# Driver_rect.net
KiCad netlist of a schematic drawn in Altium Designer
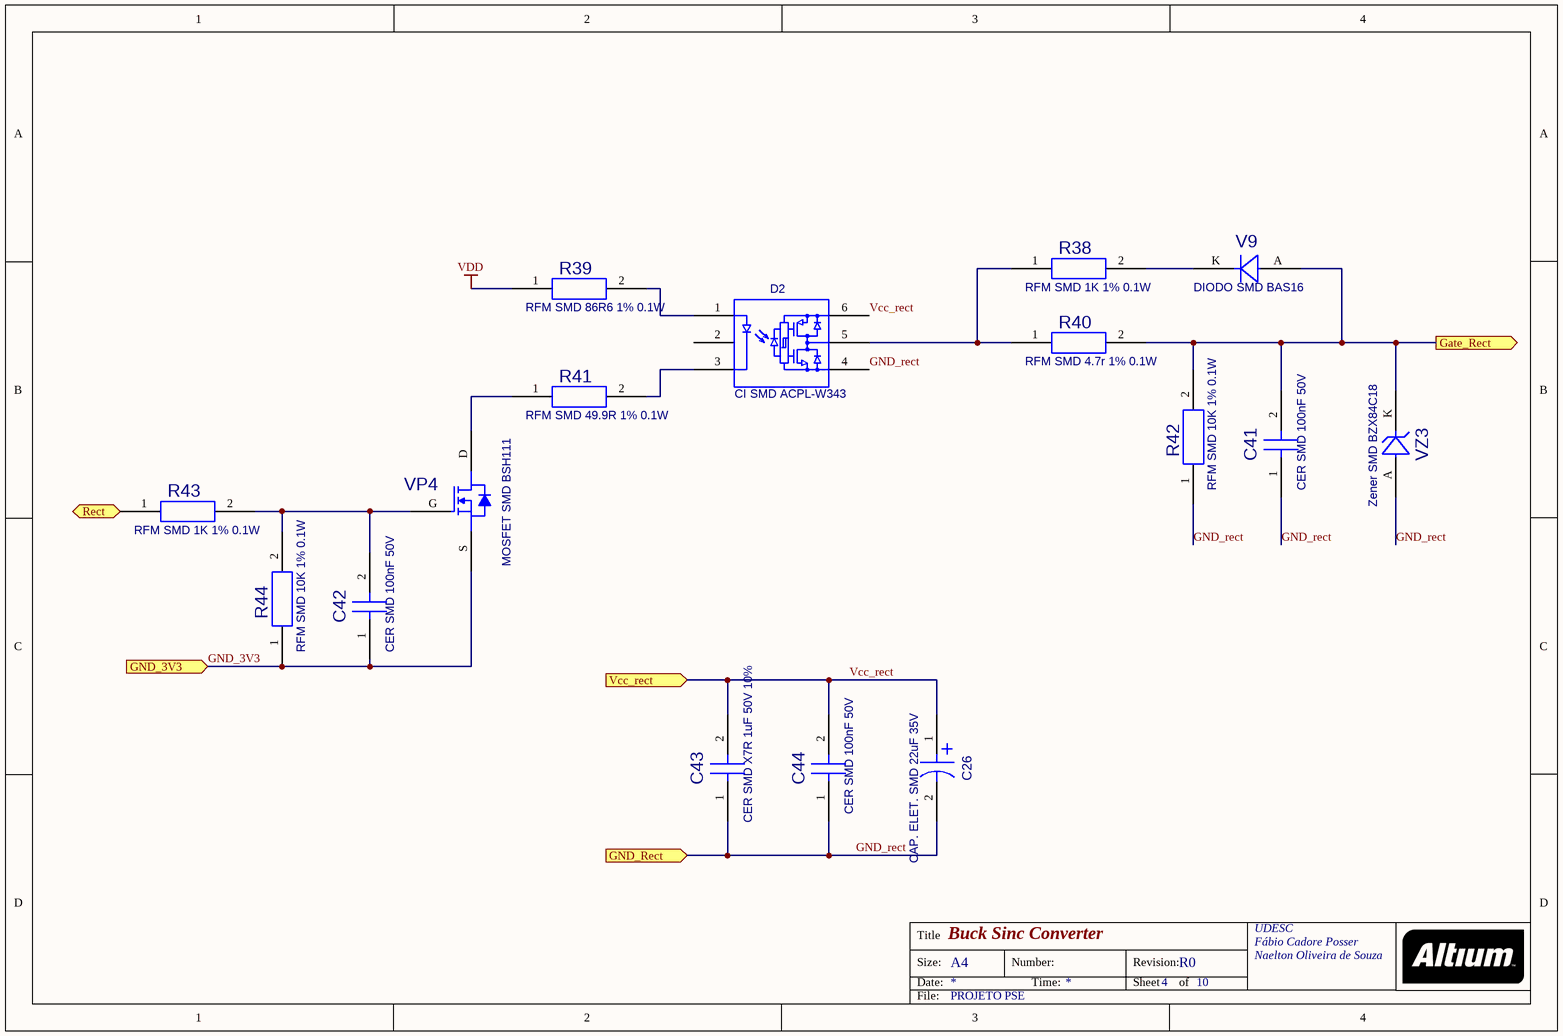
[diagram p0: Driver_rect.SchDoc]

(export (version "E")
  (design (tool "Eeschema 10.0.6"))
  (components
    (comp (ref "C26")
      (value "CAP. ELET. SMD 22uF 35V")
      (footprint "CAP UUD CR 5X5.8")
      (fields (field (name "Comment") "11690909"))
      (libsource (lib "Conv_buck_R0") (part "11690909"))
    )
    (comp (ref "C41")
      (value "CER SMD 100nF 50V")
      (footprint "C0805_R_V0")
      (fields (field (name "Comment") "10192075"))
      (libsource (lib "Buck_Converter") (part "10192075"))
    )
    (comp (ref "C42")
      (value "CER SMD 100nF 50V")
      (footprint "C0805_R_V0")
      (fields (field (name "Comment") "10192075"))
      (libsource (lib "Buck_Converter") (part "10192075"))
    )
    (comp (ref "C43")
      (value "CER SMD X7R 1uF 50V 10%")
      (footprint "C0805_R_V0")
      (fields (field (name "Comment") "11736520"))
      (libsource (lib "Buck_Converter") (part "11736520"))
    )
    (comp (ref "C44")
      (value "CER SMD 100nF 50V")
      (footprint "C0805_R_V0")
      (fields (field (name "Comment") "10192075"))
      (libsource (lib "Buck_Converter") (part "10192075"))
    )
    (comp (ref "D2")
      (value "CI SMD ACPL-W343")
      (footprint "SO-6 (11.5 MM)")
      (fields (field (name "Comment") "12544475"))
      (libsource (lib "Buck_Converter") (part "12544475"))
    )
    (comp (ref "R38")
      (value "RFM SMD 1K 1% 0.1W")
      (footprint "R0805_R_V0")
      (fields (field (name "Comment") "10118077"))
      (libsource (lib "Buck_Converter") (part "10118077"))
    )
    (comp (ref "R39")
      (value "RFM SMD 86R6 1% 0.1W")
      (footprint "R0805_R_V0")
      (fields (field (name "Comment") "10192050"))
      (libsource (lib "Buck_Converter") (part "10118077"))
    )
    (comp (ref "R40")
      (value "RFM SMD 4.7r 1% 0.1W")
      (footprint "R0805_R_V0")
      (fields (field (name "Comment") "10192015"))
      (libsource (lib "Buck_Converter") (part "10118077"))
    )
    (comp (ref "R41")
      (value "RFM SMD 49.9R 1% 0.1W")
      (footprint "R0805_R_V0")
      (fields (field (name "Comment") "10192035"))
      (libsource (lib "Buck_Converter") (part "10118077"))
    )
    (comp (ref "R42")
      (value "RFM SMD 10K 1% 0.1W")
      (footprint "R0805_R_V0")
      (fields (field (name "Comment") "10118076"))
      (libsource (lib "Buck_Converter") (part "10118077"))
    )
    (comp (ref "R43")
      (value "RFM SMD 1K 1% 0.1W")
      (footprint "R0805_R_V0")
      (fields (field (name "Comment") "10118077"))
      (libsource (lib "Buck_Converter") (part "10118077"))
    )
    (comp (ref "R44")
      (value "RFM SMD 10K 1% 0.1W")
      (footprint "R0805_R_V0")
      (fields (field (name "Comment") "10118076"))
      (libsource (lib "Buck_Converter") (part "10118077"))
    )
    (comp (ref "V9")
      (value "DIODO SMD BAS16")
      (footprint "SOT23A")
      (fields (field (name "Comment") "10261302"))
      (libsource (lib "Buck_Converter") (part "10261302"))
    )
    (comp (ref "VP4")
      (value "MOSFET SMD BSH111")
      (footprint "MOS_SOT23A")
      (fields (field (name "Comment") "11110327"))
      (libsource (lib "Buck_Converter") (part "11110327"))
    )
    (comp (ref "VZ3")
      (value "Zener SMD BZX84C18")
      (footprint "ZEN_SOT23A")
      (description "Zener  SMD BZX84C18")
      (fields (field (name "Comment") "10050447"))
      (libsource (lib "Buck_Converter") (part "10050447"))
    )
  )
  (nets
    (net (code "1") (name "/GND_3V3") (class "Default")
      (node (ref "C42") (pin "1") (pinfunction "1_1") (pintype "passive"))
      (node (ref "R44") (pin "1") (pinfunction "1_1") (pintype "passive"))
      (node (ref "VP4") (pin "S") (pinfunction "S_S") (pintype "passive"))
    )
    (net (code "2") (name "/GND_rect") (class "Default")
      (node (ref "C26") (pin "2") (pinfunction "2_2") (pintype "passive"))
      (node (ref "C41") (pin "1") (pinfunction "1_1") (pintype "passive"))
      (node (ref "C43") (pin "1") (pinfunction "1_1") (pintype "passive"))
      (node (ref "C44") (pin "1") (pinfunction "1_1") (pintype "passive"))
      (node (ref "D2") (pin "4") (pinfunction "VEE_4") (pintype "passive"))
      (node (ref "R42") (pin "1") (pinfunction "1_1") (pintype "passive"))
      (node (ref "VZ3") (pin "A") (pinfunction "A_A") (pintype "passive"))
    )
    (net (code "3") (name "/Gate_Rect") (class "Default")
      (node (ref "C41") (pin "2") (pinfunction "2_2") (pintype "passive"))
      (node (ref "R40") (pin "2") (pinfunction "2_2") (pintype "passive"))
      (node (ref "R42") (pin "2") (pinfunction "2_2") (pintype "passive"))
      (node (ref "V9") (pin "A") (pinfunction "A_A") (pintype "passive"))
      (node (ref "VZ3") (pin "K") (pinfunction "K_K") (pintype "passive"))
    )
    (net (code "4") (name "/Rect") (class "Default")
      (node (ref "R43") (pin "1") (pinfunction "1_1") (pintype "passive"))
    )
    (net (code "5") (name "/Vcc_rect") (class "Default")
      (node (ref "C26") (pin "1") (pinfunction "1_1") (pintype "passive"))
      (node (ref "C43") (pin "2") (pinfunction "2_2") (pintype "passive"))
      (node (ref "C44") (pin "2") (pinfunction "2_2") (pintype "passive"))
      (node (ref "D2") (pin "6") (pinfunction "VCC_6") (pintype "passive"))
    )
    (net (code "6") (name "Net-(C42-Pad2)") (class "Default")
      (node (ref "C42") (pin "2") (pinfunction "2_2") (pintype "passive"))
      (node (ref "R43") (pin "2") (pinfunction "2_2") (pintype "passive"))
      (node (ref "R44") (pin "2") (pinfunction "2_2") (pintype "passive"))
      (node (ref "VP4") (pin "G") (pinfunction "G_G") (pintype "passive"))
    )
    (net (code "7") (name "Net-(D2-A)") (class "Default")
      (node (ref "D2") (pin "1") (pinfunction "A_1") (pintype "passive"))
      (node (ref "R39") (pin "2") (pinfunction "2_2") (pintype "passive"))
    )
    (net (code "8") (name "Net-(D2-K)") (class "Default")
      (node (ref "D2") (pin "3") (pinfunction "K_3") (pintype "passive"))
      (node (ref "R41") (pin "2") (pinfunction "2_2") (pintype "passive"))
    )
    (net (code "9") (name "Net-(D2-VOUT)") (class "Default")
      (node (ref "D2") (pin "5") (pinfunction "VOUT_5") (pintype "passive"))
      (node (ref "R38") (pin "1") (pinfunction "1_1") (pintype "passive"))
      (node (ref "R40") (pin "1") (pinfunction "1_1") (pintype "passive"))
    )
    (net (code "10") (name "Net-(R38-Pad2)") (class "Default")
      (node (ref "R38") (pin "2") (pinfunction "2_2") (pintype "passive"))
      (node (ref "V9") (pin "K") (pinfunction "K_K") (pintype "passive"))
    )
    (net (code "11") (name "Net-(R41-Pad1)") (class "Default")
      (node (ref "R41") (pin "1") (pinfunction "1_1") (pintype "passive"))
      (node (ref "VP4") (pin "D") (pinfunction "D_D") (pintype "passive"))
    )
    (net (code "12") (name "VDD") (class "Default")
      (node (ref "R39") (pin "1") (pinfunction "1_1") (pintype "passive"))
    )
    (net (code "13") (name "unconnected-(D2-Pad2)") (class "Default")
      (node (ref "D2") (pin "2") (pinfunction "2_2") (pintype "passive"))
    )
    (net (code "14") (name "unconnected-(V9-PadNC)") (class "Default")
      (node (ref "V9") (pin "NC") (pintype "passive"))
    )
    (net (code "15") (name "unconnected-(VZ3-PadNC)") (class "Default")
      (node (ref "VZ3") (pin "NC") (pintype "passive"))
    )
  )
)
